# scartboard.net
KiCad netlist of a schematic drawn in EAGLE
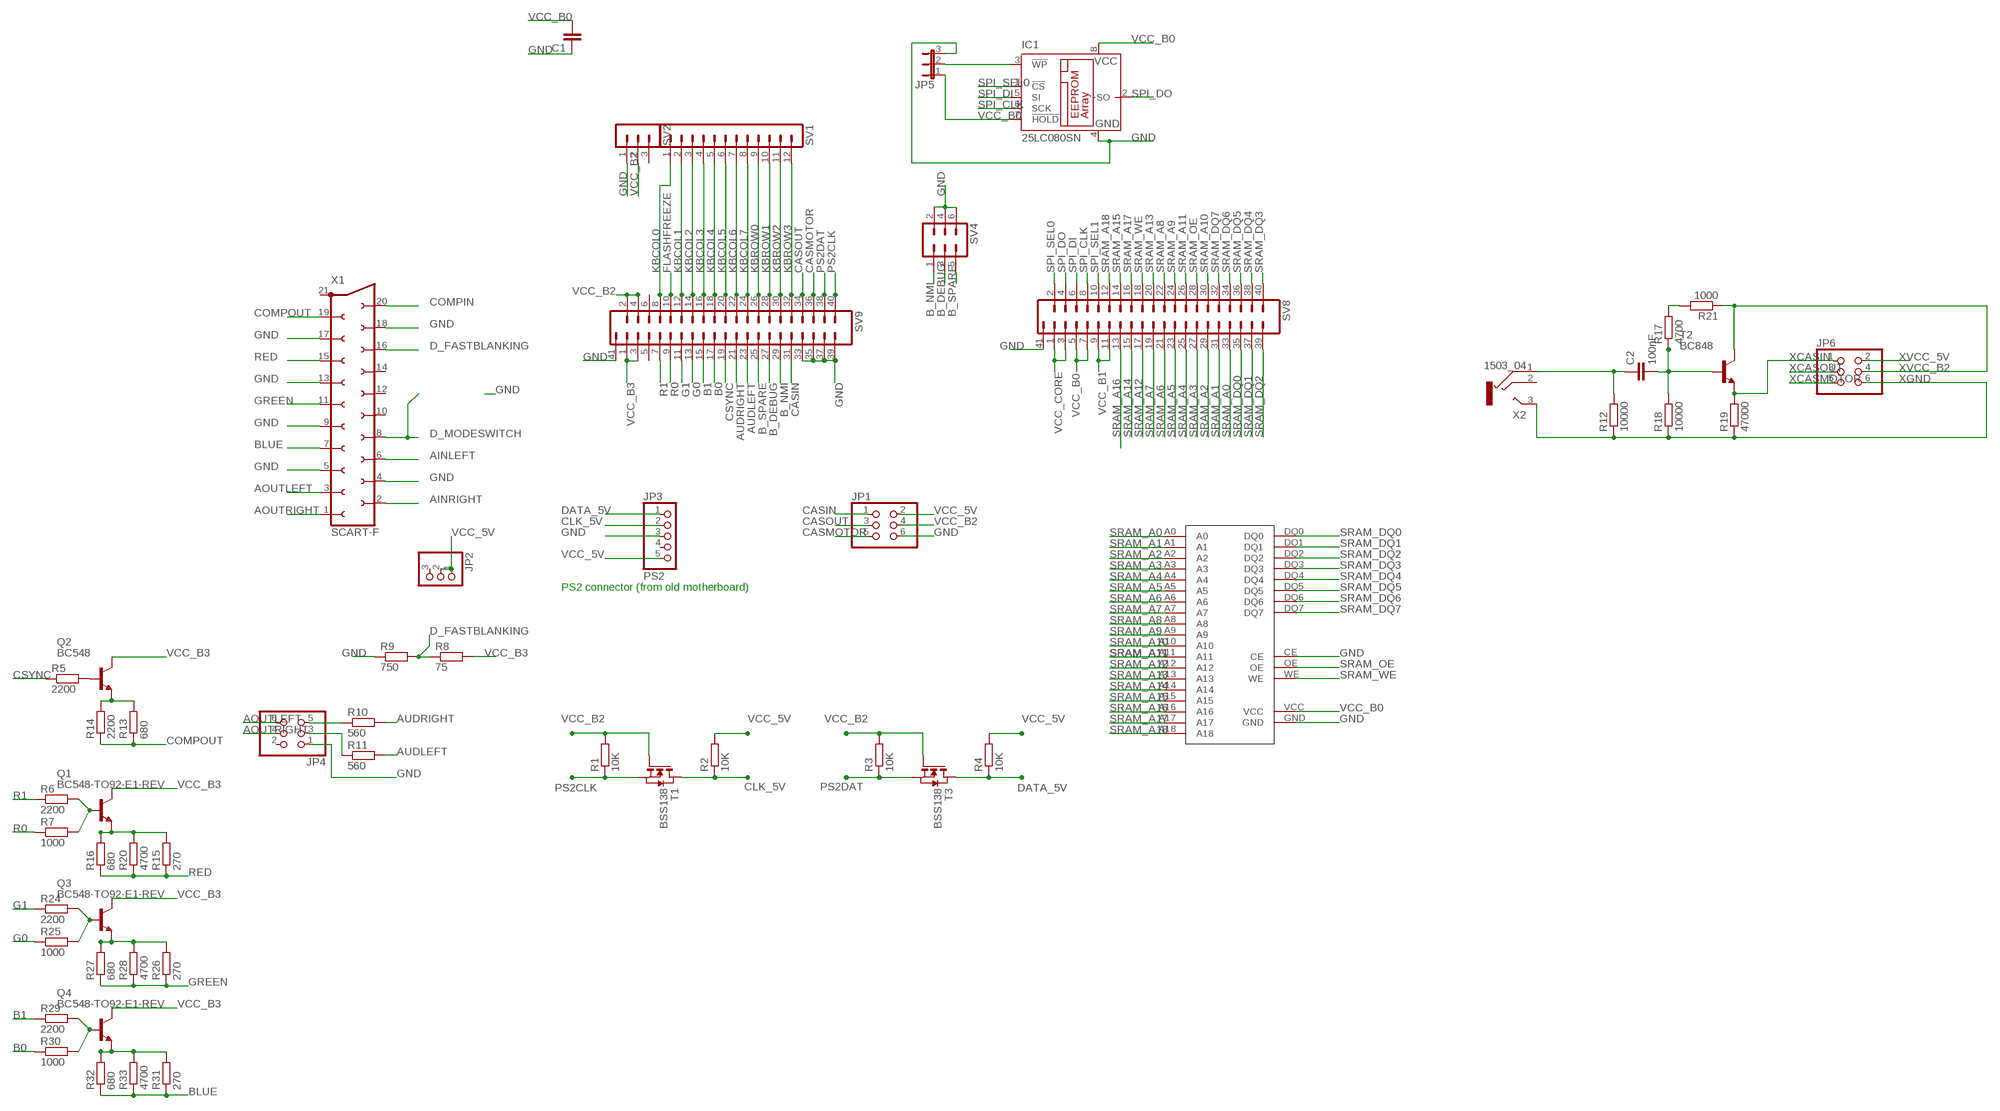
[diagram p0: schematic, sheet 1]

(export (version "E")
  (design (tool "Eeschema 10.0.6"))
  (components
    (comp (ref "C1")
      (value "C-EUC0603")
      (footprint "eagle-import:C0603")
      (libsource (lib "eagle-import") (part "C-EUC0603"))
    )
    (comp (ref "C2")
      (value "100nF")
      (footprint "eagle-import:C0603")
      (libsource (lib "eagle-import") (part "resistor_C-EUC0603"))
    )
    (comp (ref "IC1")
      (value "25LC080SN")
      (footprint "eagle-import:SO-08")
      (fields (field (name "MF") "MICROCHIP") (field (name "MPN") "25LC080/SN"))
      (libsource (lib "eagle-import") (part "25SNLC080"))
    )
    (comp (ref "JP1")
      (value "PINHD-2X3")
      (footprint "eagle-import:2X03")
      (libsource (lib "eagle-import") (part "PINHD-2X3"))
    )
    (comp (ref "JP2")
      (value "PINHD-1X3")
      (footprint "eagle-import:1X03")
      (libsource (lib "eagle-import") (part "PINHD-1X3"))
    )
    (comp (ref "JP3")
      (value "PS2")
      (footprint "eagle-import:1X05")
      (libsource (lib "eagle-import") (part "PINHD-1X5"))
    )
    (comp (ref "JP4")
      (value "PINHD-2X3")
      (footprint "eagle-import:2X03")
      (libsource (lib "eagle-import") (part "PINHD-2X3"))
    )
    (comp (ref "JP5")
      (value "JP2E")
      (footprint "eagle-import:JP2")
      (libsource (lib "eagle-import") (part "JP2E"))
    )
    (comp (ref "JP6")
      (value "PINHD-2X3")
      (footprint "eagle-import:2X03")
      (libsource (lib "eagle-import") (part "PINHD-2X3"))
    )
    (comp (ref "Q1")
      (value "BC548-TO92-E1-REV")
      (footprint "eagle-import:TO92-E1-REV")
      (libsource (lib "eagle-import") (part "BC548-TO92-E1-REV"))
    )
    (comp (ref "Q2")
      (value "BC548")
      (footprint "eagle-import:TO92-EBC")
      (libsource (lib "eagle-import") (part "BC548"))
    )
    (comp (ref "Q3")
      (value "BC548-TO92-E1-REV")
      (footprint "eagle-import:TO92-E1-REV")
      (libsource (lib "eagle-import") (part "BC548-TO92-E1-REV"))
    )
    (comp (ref "Q4")
      (value "BC548-TO92-E1-REV")
      (footprint "eagle-import:TO92-E1-REV")
      (libsource (lib "eagle-import") (part "BC548-TO92-E1-REV"))
    )
    (comp (ref "R1")
      (value "10K")
      (footprint "eagle-import:R0805")
      (libsource (lib "eagle-import") (part "R-EU_R0805"))
    )
    (comp (ref "R2")
      (value "10K")
      (footprint "eagle-import:R0805")
      (libsource (lib "eagle-import") (part "R-EU_R0805"))
    )
    (comp (ref "R3")
      (value "10K")
      (footprint "eagle-import:R0805")
      (libsource (lib "eagle-import") (part "R-EU_R0805"))
    )
    (comp (ref "R4")
      (value "10K")
      (footprint "eagle-import:R0805")
      (libsource (lib "eagle-import") (part "R-EU_R0805"))
    )
    (comp (ref "R5")
      (value "2200")
      (footprint "eagle-import:R0805")
      (libsource (lib "eagle-import") (part "R-EU_R0805"))
    )
    (comp (ref "R6")
      (value "2200")
      (footprint "eagle-import:R0805")
      (libsource (lib "eagle-import") (part "R-EU_R0805"))
    )
    (comp (ref "R7")
      (value "1000")
      (footprint "eagle-import:R0805")
      (libsource (lib "eagle-import") (part "R-EU_R0805"))
    )
    (comp (ref "R8")
      (value "75")
      (footprint "eagle-import:R0805")
      (libsource (lib "eagle-import") (part "R-EU_R0805"))
    )
    (comp (ref "R9")
      (value "750")
      (footprint "eagle-import:R0805")
      (libsource (lib "eagle-import") (part "R-EU_R0805"))
    )
    (comp (ref "R10")
      (value "560")
      (footprint "eagle-import:R0805")
      (libsource (lib "eagle-import") (part "R-EU_R0805"))
    )
    (comp (ref "R11")
      (value "560")
      (footprint "eagle-import:R0805")
      (libsource (lib "eagle-import") (part "R-EU_R0805"))
    )
    (comp (ref "R12")
      (value "10000")
      (footprint "eagle-import:R0805")
      (libsource (lib "eagle-import") (part "R-EU_R0805"))
    )
    (comp (ref "R13")
      (value "680")
      (footprint "eagle-import:R0805")
      (libsource (lib "eagle-import") (part "R-EU_R0805"))
    )
    (comp (ref "R14")
      (value "2200")
      (footprint "eagle-import:R0805")
      (libsource (lib "eagle-import") (part "R-EU_R0805"))
    )
    (comp (ref "R15")
      (value "270")
      (footprint "eagle-import:R0805")
      (libsource (lib "eagle-import") (part "R-EU_R0805"))
    )
    (comp (ref "R16")
      (value "680")
      (footprint "eagle-import:R0805")
      (libsource (lib "eagle-import") (part "R-EU_R0805"))
    )
    (comp (ref "R17")
      (value "4700")
      (footprint "eagle-import:R0805")
      (libsource (lib "eagle-import") (part "R-EU_R0805"))
    )
    (comp (ref "R18")
      (value "10000")
      (footprint "eagle-import:R0805")
      (libsource (lib "eagle-import") (part "R-EU_R0805"))
    )
    (comp (ref "R19")
      (value "47000")
      (footprint "eagle-import:R0805")
      (libsource (lib "eagle-import") (part "R-EU_R0805"))
    )
    (comp (ref "R20")
      (value "4700")
      (footprint "eagle-import:R0805")
      (libsource (lib "eagle-import") (part "R-EU_R0805"))
    )
    (comp (ref "R21")
      (value "1000")
      (footprint "eagle-import:R0805")
      (libsource (lib "eagle-import") (part "R-EU_R0805"))
    )
    (comp (ref "R24")
      (value "2200")
      (footprint "eagle-import:R0805")
      (libsource (lib "eagle-import") (part "R-EU_R0805"))
    )
    (comp (ref "R25")
      (value "1000")
      (footprint "eagle-import:R0805")
      (libsource (lib "eagle-import") (part "R-EU_R0805"))
    )
    (comp (ref "R26")
      (value "270")
      (footprint "eagle-import:R0805")
      (libsource (lib "eagle-import") (part "R-EU_R0805"))
    )
    (comp (ref "R27")
      (value "680")
      (footprint "eagle-import:R0805")
      (libsource (lib "eagle-import") (part "R-EU_R0805"))
    )
    (comp (ref "R28")
      (value "4700")
      (footprint "eagle-import:R0805")
      (libsource (lib "eagle-import") (part "R-EU_R0805"))
    )
    (comp (ref "R29")
      (value "2200")
      (footprint "eagle-import:R0805")
      (libsource (lib "eagle-import") (part "R-EU_R0805"))
    )
    (comp (ref "R30")
      (value "1000")
      (footprint "eagle-import:R0805")
      (libsource (lib "eagle-import") (part "R-EU_R0805"))
    )
    (comp (ref "R31")
      (value "270")
      (footprint "eagle-import:R0805")
      (libsource (lib "eagle-import") (part "R-EU_R0805"))
    )
    (comp (ref "R32")
      (value "680")
      (footprint "eagle-import:R0805")
      (libsource (lib "eagle-import") (part "R-EU_R0805"))
    )
    (comp (ref "R33")
      (value "4700")
      (footprint "eagle-import:R0805")
      (libsource (lib "eagle-import") (part "R-EU_R0805"))
    )
    (comp (ref "SV1")
      (value "MA12-1")
      (footprint "eagle-import:MA12-1")
      (libsource (lib "eagle-import") (part "MA12-1"))
    )
    (comp (ref "SV2")
      (value "MA03-1")
      (footprint "eagle-import:MA03-1")
      (libsource (lib "eagle-import") (part "MA03-1"))
    )
    (comp (ref "SV4")
      (value "MA03-2")
      (footprint "eagle-import:MA03-2")
      (libsource (lib "eagle-import") (part "MA03-2"))
    )
    (comp (ref "SV8")
      (value "ACTEL_HDR")
      (footprint "eagle-import:ACTEL_HDR")
      (libsource (lib "eagle-import") (part "ACTEL_HDR"))
    )
    (comp (ref "SV9")
      (value "ACTEL_HDR")
      (footprint "eagle-import:ACTEL_HDR")
      (libsource (lib "eagle-import") (part "ACTEL_HDR"))
    )
    (comp (ref "T1")
      (value "BSS138")
      (footprint "eagle-import:SOT-23")
      (libsource (lib "eagle-import") (part "NMOSSOT23"))
    )
    (comp (ref "T2")
      (value "BC848")
      (footprint "eagle-import:SOT23")
      (libsource (lib "eagle-import") (part "BC848"))
    )
    (comp (ref "T3")
      (value "BSS138")
      (footprint "eagle-import:SOT-23")
      (libsource (lib "eagle-import") (part "NMOSSOT23"))
    )
    (comp (ref "U$1")
      (value "AS6C4008")
      (footprint "eagle-import:SOP32")
      (libsource (lib "eagle-import") (part "AS6C4008"))
    )
    (comp (ref "X1")
      (value "SCART-F")
      (footprint "eagle-import:SCART-F")
      (libsource (lib "eagle-import") (part "SCART-F"))
    )
    (comp (ref "X2")
      (value "1503_04")
      (footprint "eagle-import:1503_04")
      (libsource (lib "eagle-import") (part "1503_04"))
    )
  )
  (nets
    (net (code "1") (name "/AINLEFT") (class "Default")
      (node (ref "X1") (pin "6") (pinfunction "6_6") (pintype "passive"))
    )
    (net (code "2") (name "/AINRIGHT") (class "Default")
      (node (ref "X1") (pin "2") (pinfunction "2_2") (pintype "passive"))
    )
    (net (code "3") (name "/AOUTLEFT") (class "Default")
      (node (ref "JP4") (pin "6") (pinfunction "6_6") (pintype "passive"))
      (node (ref "X1") (pin "3") (pinfunction "3_3") (pintype "passive"))
    )
    (net (code "4") (name "/AOUTRIGHT") (class "Default")
      (node (ref "JP4") (pin "4") (pinfunction "4_4") (pintype "passive"))
      (node (ref "X1") (pin "1") (pinfunction "1_1") (pintype "passive"))
    )
    (net (code "5") (name "/AUDLEFT") (class "Default")
      (node (ref "R11") (pin "2") (pinfunction "2_2") (pintype "passive"))
      (node (ref "SV9") (pin "23") (pinfunction "23_23") (pintype "passive"))
    )
    (net (code "6") (name "/AUDRIGHT") (class "Default")
      (node (ref "R10") (pin "2") (pinfunction "2_2") (pintype "passive"))
      (node (ref "SV9") (pin "21") (pinfunction "21_21") (pintype "passive"))
    )
    (net (code "7") (name "/B0") (class "Default")
      (node (ref "R30") (pin "1") (pinfunction "1_1") (pintype "passive"))
      (node (ref "SV9") (pin "17") (pinfunction "17_17") (pintype "passive"))
    )
    (net (code "8") (name "/B1") (class "Default")
      (node (ref "R29") (pin "1") (pinfunction "1_1") (pintype "passive"))
      (node (ref "SV9") (pin "15") (pinfunction "15_15") (pintype "passive"))
    )
    (net (code "9") (name "/BLUE") (class "Default")
      (node (ref "R31") (pin "1") (pinfunction "1_1") (pintype "passive"))
      (node (ref "R32") (pin "1") (pinfunction "1_1") (pintype "passive"))
      (node (ref "R33") (pin "1") (pinfunction "1_1") (pintype "passive"))
      (node (ref "X1") (pin "7") (pinfunction "7_7") (pintype "passive"))
    )
    (net (code "10") (name "/B_DEBUG") (class "Default")
      (node (ref "SV4") (pin "3") (pinfunction "3_3") (pintype "passive"))
      (node (ref "SV9") (pin "27") (pinfunction "27_27") (pintype "passive"))
    )
    (net (code "11") (name "/B_NMI") (class "Default")
      (node (ref "SV4") (pin "1") (pinfunction "1_1") (pintype "passive"))
      (node (ref "SV9") (pin "29") (pinfunction "29_29") (pintype "passive"))
    )
    (net (code "12") (name "/B_SPARE") (class "Default")
      (node (ref "SV4") (pin "5") (pinfunction "5_5") (pintype "passive"))
      (node (ref "SV9") (pin "25") (pinfunction "25_25") (pintype "passive"))
    )
    (net (code "13") (name "/CASIN") (class "Default")
      (node (ref "JP1") (pin "1") (pinfunction "1_1") (pintype "passive"))
      (node (ref "SV9") (pin "31") (pinfunction "31_31") (pintype "passive"))
    )
    (net (code "14") (name "/CASMOTOR") (class "Default")
      (node (ref "JP1") (pin "5") (pinfunction "5_5") (pintype "passive"))
      (node (ref "SV9") (pin "36") (pinfunction "36_36") (pintype "passive"))
    )
    (net (code "15") (name "/CASOUT") (class "Default")
      (node (ref "JP1") (pin "3") (pinfunction "3_3") (pintype "passive"))
      (node (ref "SV9") (pin "34") (pinfunction "34_34") (pintype "passive"))
    )
    (net (code "16") (name "/CLK_5V") (class "Default")
      (node (ref "JP3") (pin "2") (pinfunction "2_2") (pintype "passive"))
      (node (ref "R2") (pin "1") (pinfunction "1_1") (pintype "passive"))
      (node (ref "T1") (pin "1") (pinfunction "D_1") (pintype "passive"))
    )
    (net (code "17") (name "/COMPIN") (class "Default")
      (node (ref "X1") (pin "20") (pinfunction "20_20") (pintype "passive"))
    )
    (net (code "18") (name "/COMPOUT") (class "Default")
      (node (ref "R13") (pin "1") (pinfunction "1_1") (pintype "passive"))
      (node (ref "R14") (pin "1") (pinfunction "1_1") (pintype "passive"))
      (node (ref "X1") (pin "19") (pinfunction "19_19") (pintype "passive"))
    )
    (net (code "19") (name "/CSYNC") (class "Default")
      (node (ref "R5") (pin "1") (pinfunction "1_1") (pintype "passive"))
      (node (ref "SV9") (pin "19") (pinfunction "19_19") (pintype "passive"))
    )
    (net (code "20") (name "/DATA_5V") (class "Default")
      (node (ref "JP3") (pin "1") (pinfunction "1_1") (pintype "passive"))
      (node (ref "R4") (pin "1") (pinfunction "1_1") (pintype "passive"))
      (node (ref "T3") (pin "1") (pinfunction "D_1") (pintype "passive"))
    )
    (net (code "21") (name "/D_FASTBLANKING") (class "Default")
      (node (ref "R8") (pin "1") (pinfunction "1_1") (pintype "passive"))
      (node (ref "R9") (pin "2") (pinfunction "2_2") (pintype "passive"))
      (node (ref "X1") (pin "16") (pinfunction "16_16") (pintype "passive"))
    )
    (net (code "22") (name "/D_MODESWITCH") (class "Default")
      (node (ref "X1") (pin "8") (pinfunction "8_8") (pintype "passive"))
    )
    (net (code "23") (name "/FLASHFREEZE") (class "Default")
      (node (ref "SV9") (pin "10") (pinfunction "10_10") (pintype "passive"))
    )
    (net (code "24") (name "/G0") (class "Default")
      (node (ref "R25") (pin "1") (pinfunction "1_1") (pintype "passive"))
      (node (ref "SV9") (pin "13") (pinfunction "13_13") (pintype "passive"))
    )
    (net (code "25") (name "/G1") (class "Default")
      (node (ref "R24") (pin "1") (pinfunction "1_1") (pintype "passive"))
      (node (ref "SV9") (pin "11") (pinfunction "11_11") (pintype "passive"))
    )
    (net (code "26") (name "/GND") (class "Default")
      (node (ref "C1") (pin "1") (pinfunction "1_1") (pintype "passive"))
      (node (ref "IC1") (pin "4") (pinfunction "GND_4") (pintype "power_in"))
      (node (ref "JP1") (pin "6") (pinfunction "6_6") (pintype "passive"))
      (node (ref "JP3") (pin "3") (pinfunction "3_3") (pintype "passive"))
      (node (ref "JP4") (pin "1") (pinfunction "1_1") (pintype "passive"))
      (node (ref "JP5") (pin "3") (pinfunction "3_3") (pintype "passive"))
      (node (ref "R9") (pin "1") (pinfunction "1_1") (pintype "passive"))
      (node (ref "SV2") (pin "1") (pinfunction "1_1") (pintype "passive"))
      (node (ref "SV4") (pin "2") (pinfunction "2_2") (pintype "passive"))
      (node (ref "SV4") (pin "4") (pinfunction "4_4") (pintype "passive"))
      (node (ref "SV4") (pin "6") (pinfunction "6_6") (pintype "passive"))
      (node (ref "SV8") (pin "41") (pinfunction "41_41") (pintype "passive"))
      (node (ref "SV9") (pin "33") (pinfunction "33_33") (pintype "passive"))
      (node (ref "SV9") (pin "35") (pinfunction "35_35") (pintype "passive"))
      (node (ref "SV9") (pin "37") (pinfunction "37_37") (pintype "passive"))
      (node (ref "SV9") (pin "39") (pinfunction "39_39") (pintype "passive"))
      (node (ref "SV9") (pin "41") (pinfunction "41_41") (pintype "passive"))
      (node (ref "U$1") (pin "CE") (pinfunction "CE_CE") (pintype "bidirectional"))
      (node (ref "U$1") (pin "GND") (pinfunction "GND_GND") (pintype "bidirectional"))
      (node (ref "X1") (pin "13") (pinfunction "13_13") (pintype "passive"))
      (node (ref "X1") (pin "17") (pinfunction "17_17") (pintype "passive"))
      (node (ref "X1") (pin "18") (pinfunction "18_18") (pintype "passive"))
      (node (ref "X1") (pin "4") (pinfunction "4_4") (pintype "passive"))
      (node (ref "X1") (pin "5") (pinfunction "5_5") (pintype "passive"))
      (node (ref "X1") (pin "9") (pinfunction "9_9") (pintype "passive"))
    )
    (net (code "27") (name "/GREEN") (class "Default")
      (node (ref "R26") (pin "1") (pinfunction "1_1") (pintype "passive"))
      (node (ref "R27") (pin "1") (pinfunction "1_1") (pintype "passive"))
      (node (ref "R28") (pin "1") (pinfunction "1_1") (pintype "passive"))
      (node (ref "X1") (pin "11") (pinfunction "11_11") (pintype "passive"))
    )
    (net (code "28") (name "/KBCOL0") (class "Default")
      (node (ref "SV1") (pin "1") (pinfunction "1_1") (pintype "passive"))
      (node (ref "SV9") (pin "8") (pinfunction "8_8") (pintype "passive"))
    )
    (net (code "29") (name "/KBCOL1") (class "Default")
      (node (ref "SV1") (pin "2") (pinfunction "2_2") (pintype "passive"))
      (node (ref "SV9") (pin "12") (pinfunction "12_12") (pintype "passive"))
    )
    (net (code "30") (name "/KBCOL2") (class "Default")
      (node (ref "SV1") (pin "3") (pinfunction "3_3") (pintype "passive"))
      (node (ref "SV9") (pin "14") (pinfunction "14_14") (pintype "passive"))
    )
    (net (code "31") (name "/KBCOL3") (class "Default")
      (node (ref "SV1") (pin "4") (pinfunction "4_4") (pintype "passive"))
      (node (ref "SV9") (pin "16") (pinfunction "16_16") (pintype "passive"))
    )
    (net (code "32") (name "/KBCOL4") (class "Default")
      (node (ref "SV1") (pin "5") (pinfunction "5_5") (pintype "passive"))
      (node (ref "SV9") (pin "18") (pinfunction "18_18") (pintype "passive"))
    )
    (net (code "33") (name "/KBCOL5") (class "Default")
      (node (ref "SV1") (pin "6") (pinfunction "6_6") (pintype "passive"))
      (node (ref "SV9") (pin "20") (pinfunction "20_20") (pintype "passive"))
    )
    (net (code "34") (name "/KBCOL6") (class "Default")
      (node (ref "SV1") (pin "7") (pinfunction "7_7") (pintype "passive"))
      (node (ref "SV9") (pin "22") (pinfunction "22_22") (pintype "passive"))
    )
    (net (code "35") (name "/KBCOL7") (class "Default")
      (node (ref "SV1") (pin "8") (pinfunction "8_8") (pintype "passive"))
      (node (ref "SV9") (pin "24") (pinfunction "24_24") (pintype "passive"))
    )
    (net (code "36") (name "/KBROW0") (class "Default")
      (node (ref "SV1") (pin "9") (pinfunction "9_9") (pintype "passive"))
      (node (ref "SV9") (pin "26") (pinfunction "26_26") (pintype "passive"))
    )
    (net (code "37") (name "/KBROW1") (class "Default")
      (node (ref "SV1") (pin "10") (pinfunction "10_10") (pintype "passive"))
      (node (ref "SV9") (pin "28") (pinfunction "28_28") (pintype "passive"))
    )
    (net (code "38") (name "/KBROW2") (class "Default")
      (node (ref "SV1") (pin "11") (pinfunction "11_11") (pintype "passive"))
      (node (ref "SV9") (pin "30") (pinfunction "30_30") (pintype "passive"))
    )
    (net (code "39") (name "/KBROW3") (class "Default")
      (node (ref "SV1") (pin "12") (pinfunction "12_12") (pintype "passive"))
      (node (ref "SV9") (pin "32") (pinfunction "32_32") (pintype "passive"))
    )
    (net (code "40") (name "/PS2CLK") (class "Default")
      (node (ref "R1") (pin "1") (pinfunction "1_1") (pintype "passive"))
      (node (ref "SV9") (pin "40") (pinfunction "40_40") (pintype "passive"))
      (node (ref "T1") (pin "2") (pinfunction "S_2") (pintype "passive"))
    )
    (net (code "41") (name "/PS2DAT") (class "Default")
      (node (ref "R3") (pin "1") (pinfunction "1_1") (pintype "passive"))
      (node (ref "SV9") (pin "38") (pinfunction "38_38") (pintype "passive"))
      (node (ref "T3") (pin "2") (pinfunction "S_2") (pintype "passive"))
    )
    (net (code "42") (name "/R0") (class "Default")
      (node (ref "R7") (pin "1") (pinfunction "1_1") (pintype "passive"))
      (node (ref "SV9") (pin "9") (pinfunction "9_9") (pintype "passive"))
    )
    (net (code "43") (name "/R1") (class "Default")
      (node (ref "R6") (pin "1") (pinfunction "1_1") (pintype "passive"))
      (node (ref "SV9") (pin "7") (pinfunction "7_7") (pintype "passive"))
    )
    (net (code "44") (name "/RED") (class "Default")
      (node (ref "R15") (pin "1") (pinfunction "1_1") (pintype "passive"))
      (node (ref "R16") (pin "1") (pinfunction "1_1") (pintype "passive"))
      (node (ref "R20") (pin "1") (pinfunction "1_1") (pintype "passive"))
      (node (ref "X1") (pin "15") (pinfunction "15_15") (pintype "passive"))
    )
    (net (code "45") (name "/SPI_CLK") (class "Default")
      (node (ref "IC1") (pin "6") (pinfunction "SCK_6") (pintype "input"))
      (node (ref "SV8") (pin "8") (pinfunction "8_8") (pintype "passive"))
    )
    (net (code "46") (name "/SPI_DI") (class "Default")
      (node (ref "IC1") (pin "5") (pinfunction "SI_5") (pintype "input"))
      (node (ref "SV8") (pin "6") (pinfunction "6_6") (pintype "passive"))
    )
    (net (code "47") (name "/SPI_DO") (class "Default")
      (node (ref "IC1") (pin "2") (pinfunction "SO_2") (pintype "bidirectional"))
      (node (ref "SV8") (pin "4") (pinfunction "4_4") (pintype "passive"))
    )
    (net (code "48") (name "/SPI_SEL0") (class "Default")
      (node (ref "IC1") (pin "1") (pinfunction "~{CS}_1") (pintype "input"))
      (node (ref "SV8") (pin "2") (pinfunction "2_2") (pintype "passive"))
    )
    (net (code "49") (name "/SPI_SEL1") (class "Default")
      (node (ref "SV8") (pin "10") (pinfunction "10_10") (pintype "passive"))
    )
    (net (code "50") (name "/SRAM_A0") (class "Default")
      (node (ref "SV8") (pin "33") (pinfunction "33_33") (pintype "passive"))
      (node (ref "U$1") (pin "A0") (pinfunction "A0_A0") (pintype "bidirectional"))
    )
    (net (code "51") (name "/SRAM_A1") (class "Default")
      (node (ref "SV8") (pin "31") (pinfunction "31_31") (pintype "passive"))
      (node (ref "U$1") (pin "A1") (pinfunction "A1_A1") (pintype "bidirectional"))
    )
    (net (code "52") (name "/SRAM_A2") (class "Default")
      (node (ref "SV8") (pin "29") (pinfunction "29_29") (pintype "passive"))
      (node (ref "U$1") (pin "A2") (pinfunction "A2_A2") (pintype "bidirectional"))
    )
    (net (code "53") (name "/SRAM_A3") (class "Default")
      (node (ref "SV8") (pin "27") (pinfunction "27_27") (pintype "passive"))
      (node (ref "U$1") (pin "A3") (pinfunction "A3_A3") (pintype "bidirectional"))
    )
    (net (code "54") (name "/SRAM_A4") (class "Default")
      (node (ref "SV8") (pin "25") (pinfunction "25_25") (pintype "passive"))
      (node (ref "U$1") (pin "A4") (pinfunction "A4_A4") (pintype "bidirectional"))
    )
    (net (code "55") (name "/SRAM_A5") (class "Default")
      (node (ref "SV8") (pin "23") (pinfunction "23_23") (pintype "passive"))
      (node (ref "U$1") (pin "A5") (pinfunction "A5_A5") (pintype "bidirectional"))
    )
    (net (code "56") (name "/SRAM_A6") (class "Default")
      (node (ref "SV8") (pin "21") (pinfunction "21_21") (pintype "passive"))
      (node (ref "U$1") (pin "A6") (pinfunction "A6_A6") (pintype "bidirectional"))
    )
    (net (code "57") (name "/SRAM_A7") (class "Default")
      (node (ref "SV8") (pin "19") (pinfunction "19_19") (pintype "passive"))
      (node (ref "U$1") (pin "A7") (pinfunction "A7_A7") (pintype "bidirectional"))
    )
    (net (code "58") (name "/SRAM_A8") (class "Default")
      (node (ref "SV8") (pin "22") (pinfunction "22_22") (pintype "passive"))
      (node (ref "U$1") (pin "A8") (pinfunction "A8_A8") (pintype "bidirectional"))
    )
    (net (code "59") (name "/SRAM_A9") (class "Default")
      (node (ref "SV8") (pin "24") (pinfunction "24_24") (pintype "passive"))
      (node (ref "U$1") (pin "A9") (pinfunction "A9_A9") (pintype "bidirectional"))
    )
    (net (code "60") (name "/SRAM_A10") (class "Default")
      (node (ref "SV8") (pin "30") (pinfunction "30_30") (pintype "passive"))
      (node (ref "U$1") (pin "A10") (pinfunction "A10_A10") (pintype "bidirectional"))
    )
    (net (code "61") (name "/SRAM_A11") (class "Default")
      (node (ref "SV8") (pin "26") (pinfunction "26_26") (pintype "passive"))
      (node (ref "U$1") (pin "A11") (pinfunction "A11_A11") (pintype "bidirectional"))
    )
    (net (code "62") (name "/SRAM_A12") (class "Default")
      (node (ref "SV8") (pin "17") (pinfunction "17_17") (pintype "passive"))
      (node (ref "U$1") (pin "A12") (pinfunction "A12_A12") (pintype "bidirectional"))
    )
    (net (code "63") (name "/SRAM_A13") (class "Default")
      (node (ref "SV8") (pin "20") (pinfunction "20_20") (pintype "passive"))
      (node (ref "U$1") (pin "A13") (pinfunction "A13_A13") (pintype "bidirectional"))
    )
    (net (code "64") (name "/SRAM_A14") (class "Default")
      (node (ref "SV8") (pin "15") (pinfunction "15_15") (pintype "passive"))
      (node (ref "U$1") (pin "A14") (pinfunction "A14_A14") (pintype "bidirectional"))
    )
    (net (code "65") (name "/SRAM_A15") (class "Default")
      (node (ref "SV8") (pin "14") (pinfunction "14_14") (pintype "passive"))
      (node (ref "U$1") (pin "A15") (pinfunction "A15_A15") (pintype "bidirectional"))
    )
    (net (code "66") (name "/SRAM_A16") (class "Default")
      (node (ref "SV8") (pin "13") (pinfunction "13_13") (pintype "passive"))
      (node (ref "U$1") (pin "A16") (pinfunction "A16_A16") (pintype "bidirectional"))
    )
    (net (code "67") (name "/SRAM_A17") (class "Default")
      (node (ref "SV8") (pin "16") (pinfunction "16_16") (pintype "passive"))
      (node (ref "U$1") (pin "A17") (pinfunction "A17_A17") (pintype "bidirectional"))
    )
    (net (code "68") (name "/SRAM_A18") (class "Default")
      (node (ref "SV8") (pin "12") (pinfunction "12_12") (pintype "passive"))
      (node (ref "U$1") (pin "A18") (pinfunction "A18_A18") (pintype "bidirectional"))
    )
    (net (code "69") (name "/SRAM_DQ0") (class "Default")
      (node (ref "SV8") (pin "35") (pinfunction "35_35") (pintype "passive"))
      (node (ref "U$1") (pin "DQ0") (pinfunction "DQ0_DQ0") (pintype "bidirectional"))
    )
    (net (code "70") (name "/SRAM_DQ1") (class "Default")
      (node (ref "SV8") (pin "37") (pinfunction "37_37") (pintype "passive"))
      (node (ref "U$1") (pin "DQ1") (pinfunction "DQ1_DQ1") (pintype "bidirectional"))
    )
    (net (code "71") (name "/SRAM_DQ2") (class "Default")
      (node (ref "SV8") (pin "39") (pinfunction "39_39") (pintype "passive"))
      (node (ref "U$1") (pin "DQ2") (pinfunction "DQ2_DQ2") (pintype "bidirectional"))
    )
    (net (code "72") (name "/SRAM_DQ3") (class "Default")
      (node (ref "SV8") (pin "40") (pinfunction "40_40") (pintype "passive"))
      (node (ref "U$1") (pin "DQ3") (pinfunction "DQ3_DQ3") (pintype "bidirectional"))
    )
    (net (code "73") (name "/SRAM_DQ4") (class "Default")
      (node (ref "SV8") (pin "38") (pinfunction "38_38") (pintype "passive"))
      (node (ref "U$1") (pin "DQ4") (pinfunction "DQ4_DQ4") (pintype "bidirectional"))
    )
    (net (code "74") (name "/SRAM_DQ5") (class "Default")
      (node (ref "SV8") (pin "36") (pinfunction "36_36") (pintype "passive"))
      (node (ref "U$1") (pin "DQ5") (pinfunction "DQ5_DQ5") (pintype "bidirectional"))
    )
    (net (code "75") (name "/SRAM_DQ6") (class "Default")
      (node (ref "SV8") (pin "34") (pinfunction "34_34") (pintype "passive"))
      (node (ref "U$1") (pin "DQ6") (pinfunction "DQ6_DQ6") (pintype "bidirectional"))
    )
    (net (code "76") (name "/SRAM_DQ7") (class "Default")
      (node (ref "SV8") (pin "32") (pinfunction "32_32") (pintype "passive"))
      (node (ref "U$1") (pin "DQ7") (pinfunction "DQ7_DQ7") (pintype "bidirectional"))
    )
    (net (code "77") (name "/SRAM_OE") (class "Default")
      (node (ref "SV8") (pin "28") (pinfunction "28_28") (pintype "passive"))
      (node (ref "U$1") (pin "OE") (pinfunction "OE_OE") (pintype "bidirectional"))
    )
    (net (code "78") (name "/SRAM_WE") (class "Default")
      (node (ref "SV8") (pin "18") (pinfunction "18_18") (pintype "passive"))
      (node (ref "U$1") (pin "WE") (pinfunction "WE_WE") (pintype "bidirectional"))
    )
    (net (code "79") (name "/VCC_5V") (class "Default")
      (node (ref "JP1") (pin "2") (pinfunction "2_2") (pintype "passive"))
      (node (ref "JP2") (pin "1") (pinfunction "1_1") (pintype "passive"))
      (node (ref "JP2") (pin "2") (pinfunction "2_2") (pintype "passive"))
      (node (ref "JP3") (pin "5") (pinfunction "5_5") (pintype "passive"))
      (node (ref "R2") (pin "2") (pinfunction "2_2") (pintype "passive"))
      (node (ref "R4") (pin "2") (pinfunction "2_2") (pintype "passive"))
    )
    (net (code "80") (name "/VCC_B0") (class "Default")
      (node (ref "C1") (pin "2") (pinfunction "2_2") (pintype "passive"))
      (node (ref "IC1") (pin "7") (pinfunction "~{HOLD}_7") (pintype "input"))
      (node (ref "IC1") (pin "8") (pinfunction "VCC_8") (pintype "power_in"))
      (node (ref "JP5") (pin "1") (pinfunction "1_1") (pintype "passive"))
      (node (ref "SV8") (pin "5") (pinfunction "5_5") (pintype "passive"))
      (node (ref "SV8") (pin "7") (pinfunction "7_7") (pintype "passive"))
      (node (ref "U$1") (pin "VCC") (pinfunction "VCC_VCC") (pintype "bidirectional"))
    )
    (net (code "81") (name "/VCC_B1") (class "Default")
      (node (ref "SV8") (pin "11") (pinfunction "11_11") (pintype "passive"))
      (node (ref "SV8") (pin "9") (pinfunction "9_9") (pintype "passive"))
    )
    (net (code "82") (name "/VCC_B2") (class "Default")
      (node (ref "JP1") (pin "4") (pinfunction "4_4") (pintype "passive"))
      (node (ref "R1") (pin "2") (pinfunction "2_2") (pintype "passive"))
      (node (ref "R3") (pin "2") (pinfunction "2_2") (pintype "passive"))
      (node (ref "SV2") (pin "2") (pinfunction "2_2") (pintype "passive"))
      (node (ref "SV9") (pin "2") (pinfunction "2_2") (pintype "passive"))
      (node (ref "SV9") (pin "4") (pinfunction "4_4") (pintype "passive"))
      (node (ref "T1") (pin "3") (pinfunction "G_3") (pintype "passive"))
      (node (ref "T3") (pin "3") (pinfunction "G_3") (pintype "passive"))
    )
    (net (code "83") (name "/VCC_B3") (class "Default")
      (node (ref "Q1") (pin "1") (pinfunction "C_1") (pintype "passive"))
      (node (ref "Q2") (pin "C") (pinfunction "C_C") (pintype "passive"))
      (node (ref "Q3") (pin "1") (pinfunction "C_1") (pintype "passive"))
      (node (ref "Q4") (pin "1") (pinfunction "C_1") (pintype "passive"))
      (node (ref "R8") (pin "2") (pinfunction "2_2") (pintype "passive"))
      (node (ref "SV9") (pin "1") (pinfunction "1_1") (pintype "passive"))
      (node (ref "SV9") (pin "3") (pinfunction "3_3") (pintype "passive"))
    )
    (net (code "84") (name "/VCC_CORE") (class "Default")
      (node (ref "SV8") (pin "1") (pinfunction "1_1") (pintype "passive"))
      (node (ref "SV8") (pin "3") (pinfunction "3_3") (pintype "passive"))
    )
    (net (code "85") (name "/XCASIN") (class "Default")
      (node (ref "JP6") (pin "1") (pinfunction "1_1") (pintype "passive"))
      (node (ref "R19") (pin "2") (pinfunction "2_2") (pintype "passive"))
      (node (ref "T2") (pin "2") (pinfunction "E_2") (pintype "passive"))
    )
    (net (code "86") (name "/XCASMOTOR") (class "Default")
      (node (ref "JP6") (pin "5") (pinfunction "5_5") (pintype "passive"))
    )
    (net (code "87") (name "/XCASOUT") (class "Default")
      (node (ref "JP6") (pin "3") (pinfunction "3_3") (pintype "passive"))
    )
    (net (code "88") (name "/XGND") (class "Default")
      (node (ref "JP6") (pin "6") (pinfunction "6_6") (pintype "passive"))
      (node (ref "R12") (pin "1") (pinfunction "1_1") (pintype "passive"))
      (node (ref "R18") (pin "1") (pinfunction "1_1") (pintype "passive"))
      (node (ref "R19") (pin "1") (pinfunction "1_1") (pintype "passive"))
      (node (ref "X2") (pin "3") (pinfunction "2_3") (pintype "passive"))
    )
    (net (code "89") (name "/XVCC_5V") (class "Default")
      (node (ref "JP6") (pin "2") (pinfunction "2_2") (pintype "passive"))
    )
    (net (code "90") (name "/XVCC_B2") (class "Default")
      (node (ref "JP6") (pin "4") (pinfunction "4_4") (pintype "passive"))
      (node (ref "R21") (pin "1") (pinfunction "1_1") (pintype "passive"))
      (node (ref "T2") (pin "3") (pinfunction "C_3") (pintype "passive"))
    )
    (net (code "91") (name "Net-(C2-Pad1)") (class "Default")
      (node (ref "C2") (pin "1") (pinfunction "1_1") (pintype "passive"))
      (node (ref "R12") (pin "2") (pinfunction "2_2") (pintype "passive"))
      (node (ref "X2") (pin "1") (pinfunction "1_1") (pintype "passive"))
    )
    (net (code "92") (name "Net-(IC1-~{WP})") (class "Default")
      (node (ref "IC1") (pin "3") (pinfunction "~{WP}_3") (pintype "input"))
      (node (ref "JP5") (pin "2") (pinfunction "2_2") (pintype "passive"))
    )
    (net (code "93") (name "Net-(JP4-Pad3)") (class "Default")
      (node (ref "JP4") (pin "3") (pinfunction "3_3") (pintype "passive"))
      (node (ref "R11") (pin "1") (pinfunction "1_1") (pintype "passive"))
    )
    (net (code "94") (name "Net-(JP4-Pad5)") (class "Default")
      (node (ref "JP4") (pin "5") (pinfunction "5_5") (pintype "passive"))
      (node (ref "R10") (pin "1") (pinfunction "1_1") (pintype "passive"))
    )
    (net (code "95") (name "Net-(Q1-B)") (class "Default")
      (node (ref "Q1") (pin "2") (pinfunction "B_2") (pintype "passive"))
      (node (ref "R6") (pin "2") (pinfunction "2_2") (pintype "passive"))
      (node (ref "R7") (pin "2") (pinfunction "2_2") (pintype "passive"))
    )
    (net (code "96") (name "Net-(Q1-E)") (class "Default")
      (node (ref "Q1") (pin "3") (pinfunction "E_3") (pintype "passive"))
      (node (ref "R15") (pin "2") (pinfunction "2_2") (pintype "passive"))
      (node (ref "R16") (pin "2") (pinfunction "2_2") (pintype "passive"))
      (node (ref "R20") (pin "2") (pinfunction "2_2") (pintype "passive"))
    )
    (net (code "97") (name "Net-(Q2-PadB)") (class "Default")
      (node (ref "Q2") (pin "B") (pinfunction "B_B") (pintype "passive"))
      (node (ref "R5") (pin "2") (pinfunction "2_2") (pintype "passive"))
    )
    (net (code "98") (name "Net-(Q2-PadE)") (class "Default")
      (node (ref "Q2") (pin "E") (pinfunction "E_E") (pintype "passive"))
      (node (ref "R13") (pin "2") (pinfunction "2_2") (pintype "passive"))
      (node (ref "R14") (pin "2") (pinfunction "2_2") (pintype "passive"))
    )
    (net (code "99") (name "Net-(Q3-B)") (class "Default")
      (node (ref "Q3") (pin "2") (pinfunction "B_2") (pintype "passive"))
      (node (ref "R24") (pin "2") (pinfunction "2_2") (pintype "passive"))
      (node (ref "R25") (pin "2") (pinfunction "2_2") (pintype "passive"))
    )
    (net (code "100") (name "Net-(Q3-E)") (class "Default")
      (node (ref "Q3") (pin "3") (pinfunction "E_3") (pintype "passive"))
      (node (ref "R26") (pin "2") (pinfunction "2_2") (pintype "passive"))
      (node (ref "R27") (pin "2") (pinfunction "2_2") (pintype "passive"))
      (node (ref "R28") (pin "2") (pinfunction "2_2") (pintype "passive"))
    )
    (net (code "101") (name "Net-(Q4-B)") (class "Default")
      (node (ref "Q4") (pin "2") (pinfunction "B_2") (pintype "passive"))
      (node (ref "R29") (pin "2") (pinfunction "2_2") (pintype "passive"))
      (node (ref "R30") (pin "2") (pinfunction "2_2") (pintype "passive"))
    )
    (net (code "102") (name "Net-(Q4-E)") (class "Default")
      (node (ref "Q4") (pin "3") (pinfunction "E_3") (pintype "passive"))
      (node (ref "R31") (pin "2") (pinfunction "2_2") (pintype "passive"))
      (node (ref "R32") (pin "2") (pinfunction "2_2") (pintype "passive"))
      (node (ref "R33") (pin "2") (pinfunction "2_2") (pintype "passive"))
    )
    (net (code "103") (name "Net-(R17-Pad2)") (class "Default")
      (node (ref "R17") (pin "2") (pinfunction "2_2") (pintype "passive"))
      (node (ref "R21") (pin "2") (pinfunction "2_2") (pintype "passive"))
    )
    (net (code "104") (name "Net-(T2-B)") (class "Default")
      (node (ref "C2") (pin "2") (pinfunction "2_2") (pintype "passive"))
      (node (ref "R17") (pin "1") (pinfunction "1_1") (pintype "passive"))
      (node (ref "R18") (pin "2") (pinfunction "2_2") (pintype "passive"))
      (node (ref "T2") (pin "1") (pinfunction "B_1") (pintype "passive"))
    )
    (net (code "105") (name "unconnected-(JP2-Pad3)") (class "Default")
      (node (ref "JP2") (pin "3") (pinfunction "3_3") (pintype "passive"))
    )
    (net (code "106") (name "unconnected-(JP3-Pad4)") (class "Default")
      (node (ref "JP3") (pin "4") (pinfunction "4_4") (pintype "passive"))
    )
    (net (code "107") (name "unconnected-(JP4-Pad2)") (class "Default")
      (node (ref "JP4") (pin "2") (pinfunction "2_2") (pintype "passive"))
    )
    (net (code "108") (name "unconnected-(SV2-Pad3)") (class "Default")
      (node (ref "SV2") (pin "3") (pinfunction "3_3") (pintype "passive"))
    )
    (net (code "109") (name "unconnected-(SV9-Pad5)") (class "Default")
      (node (ref "SV9") (pin "5") (pinfunction "5_5") (pintype "passive"))
    )
    (net (code "110") (name "unconnected-(SV9-Pad6)") (class "Default")
      (node (ref "SV9") (pin "6") (pinfunction "6_6") (pintype "passive"))
    )
    (net (code "111") (name "unconnected-(X1-Pad10)") (class "Default")
      (node (ref "X1") (pin "10") (pinfunction "10_10") (pintype "passive"))
    )
    (net (code "112") (name "unconnected-(X1-Pad12)") (class "Default")
      (node (ref "X1") (pin "12") (pinfunction "12_12") (pintype "passive"))
    )
    (net (code "113") (name "unconnected-(X1-Pad14)") (class "Default")
      (node (ref "X1") (pin "14") (pinfunction "14_14") (pintype "passive"))
    )
    (net (code "114") (name "unconnected-(X1-Pad21)") (class "Default")
      (node (ref "X1") (pin "21") (pinfunction "21_21") (pintype "passive"))
    )
    (net (code "115") (name "unconnected-(X2-3-Pad2)") (class "Default")
      (node (ref "X2") (pin "2") (pinfunction "3_2") (pintype "passive"))
    )
  )
)
